# Sheet3.net
KiCad netlist of a schematic drawn in Altium Designer
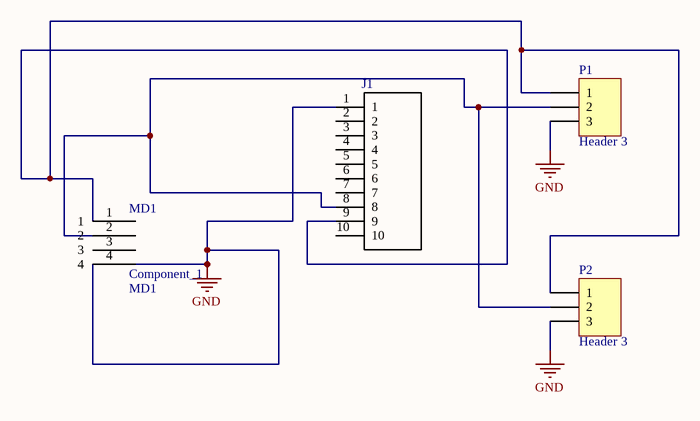
[diagram p0: Sheet3.SchDoc]

(export (version "E")
  (design (tool "Eeschema 10.0.6"))
  (components
    (comp (ref "J1")
      (value "5499913-1")
      (footprint "*TE_5499913-1")
      (description "HEADER; UNIVERSAL EJECTION PIN; AMP-LATCH; 10 POS; 2.54 X 2.54; PCB; RIGHT ANGLE")
      (fields (field (name "MF") "TE Connectivity"))
      (libsource (lib "5499913-1") (part "5499913-1"))
    )
    (comp (ref "MD1")
      (value "Component_1")
      (footprint "PCBComponent_1")
      (fields (field (name "PART NUM") "MD1"))
      (libsource (lib "cytron test 1") (part "Component_1"))
    )
    (comp (ref "P1")
      (value "Header 3")
      (footprint "HDR1X3")
      (description "Header, 3-Pin")
      (fields (field (name "PUBLISHER") "Altium Limited"))
      (libsource (lib "Miscellaneous Connectors") (part "Header 3"))
    )
    (comp (ref "P2")
      (value "Header 3")
      (footprint "HDR1X3")
      (description "Header, 3-Pin")
      (fields (field (name "PUBLISHER") "Altium Limited"))
      (libsource (lib "Miscellaneous Connectors") (part "Header 3"))
    )
  )
  (nets
    (net (code "1") (name "GND") (class "Default")
      (node (ref "J1") (pin "1") (pinfunction "1_1") (pintype "passive"))
      (node (ref "MD1") (pin "4") (pinfunction "4_4") (pintype "passive"))
      (node (ref "P1") (pin "3") (pinfunction "3_3") (pintype "passive"))
      (node (ref "P2") (pin "3") (pinfunction "3_3") (pintype "passive"))
    )
    (net (code "2") (name "Net-(J1-Pad8)") (class "Default")
      (node (ref "J1") (pin "8") (pinfunction "8_8") (pintype "passive"))
      (node (ref "MD1") (pin "2") (pinfunction "2_2") (pintype "passive"))
      (node (ref "P1") (pin "2") (pinfunction "2_2") (pintype "passive"))
      (node (ref "P2") (pin "2") (pinfunction "2_2") (pintype "passive"))
    )
    (net (code "3") (name "Net-(J1-Pad9)") (class "Default")
      (node (ref "J1") (pin "9") (pinfunction "9_9") (pintype "passive"))
      (node (ref "MD1") (pin "1") (pinfunction "1_1") (pintype "passive"))
      (node (ref "P1") (pin "1") (pinfunction "1_1") (pintype "passive"))
      (node (ref "P2") (pin "1") (pinfunction "1_1") (pintype "passive"))
    )
    (net (code "4") (name "unconnected-(J1-Pad2)") (class "Default")
      (node (ref "J1") (pin "2") (pinfunction "2_2") (pintype "passive"))
    )
    (net (code "5") (name "unconnected-(J1-Pad3)") (class "Default")
      (node (ref "J1") (pin "3") (pinfunction "3_3") (pintype "passive"))
    )
    (net (code "6") (name "unconnected-(J1-Pad4)") (class "Default")
      (node (ref "J1") (pin "4") (pinfunction "4_4") (pintype "passive"))
    )
    (net (code "7") (name "unconnected-(J1-Pad5)") (class "Default")
      (node (ref "J1") (pin "5") (pinfunction "5_5") (pintype "passive"))
    )
    (net (code "8") (name "unconnected-(J1-Pad6)") (class "Default")
      (node (ref "J1") (pin "6") (pinfunction "6_6") (pintype "passive"))
    )
    (net (code "9") (name "unconnected-(J1-Pad7)") (class "Default")
      (node (ref "J1") (pin "7") (pinfunction "7_7") (pintype "passive"))
    )
    (net (code "10") (name "unconnected-(J1-Pad10)") (class "Default")
      (node (ref "J1") (pin "10") (pinfunction "10_10") (pintype "passive"))
    )
    (net (code "11") (name "unconnected-(MD1-Pad3)") (class "Default")
      (node (ref "MD1") (pin "3") (pinfunction "3_3") (pintype "passive"))
    )
  )
)
